# ESP_LoRa_Weather_1_55.net
KiCad netlist of a schematic drawn in EAGLE
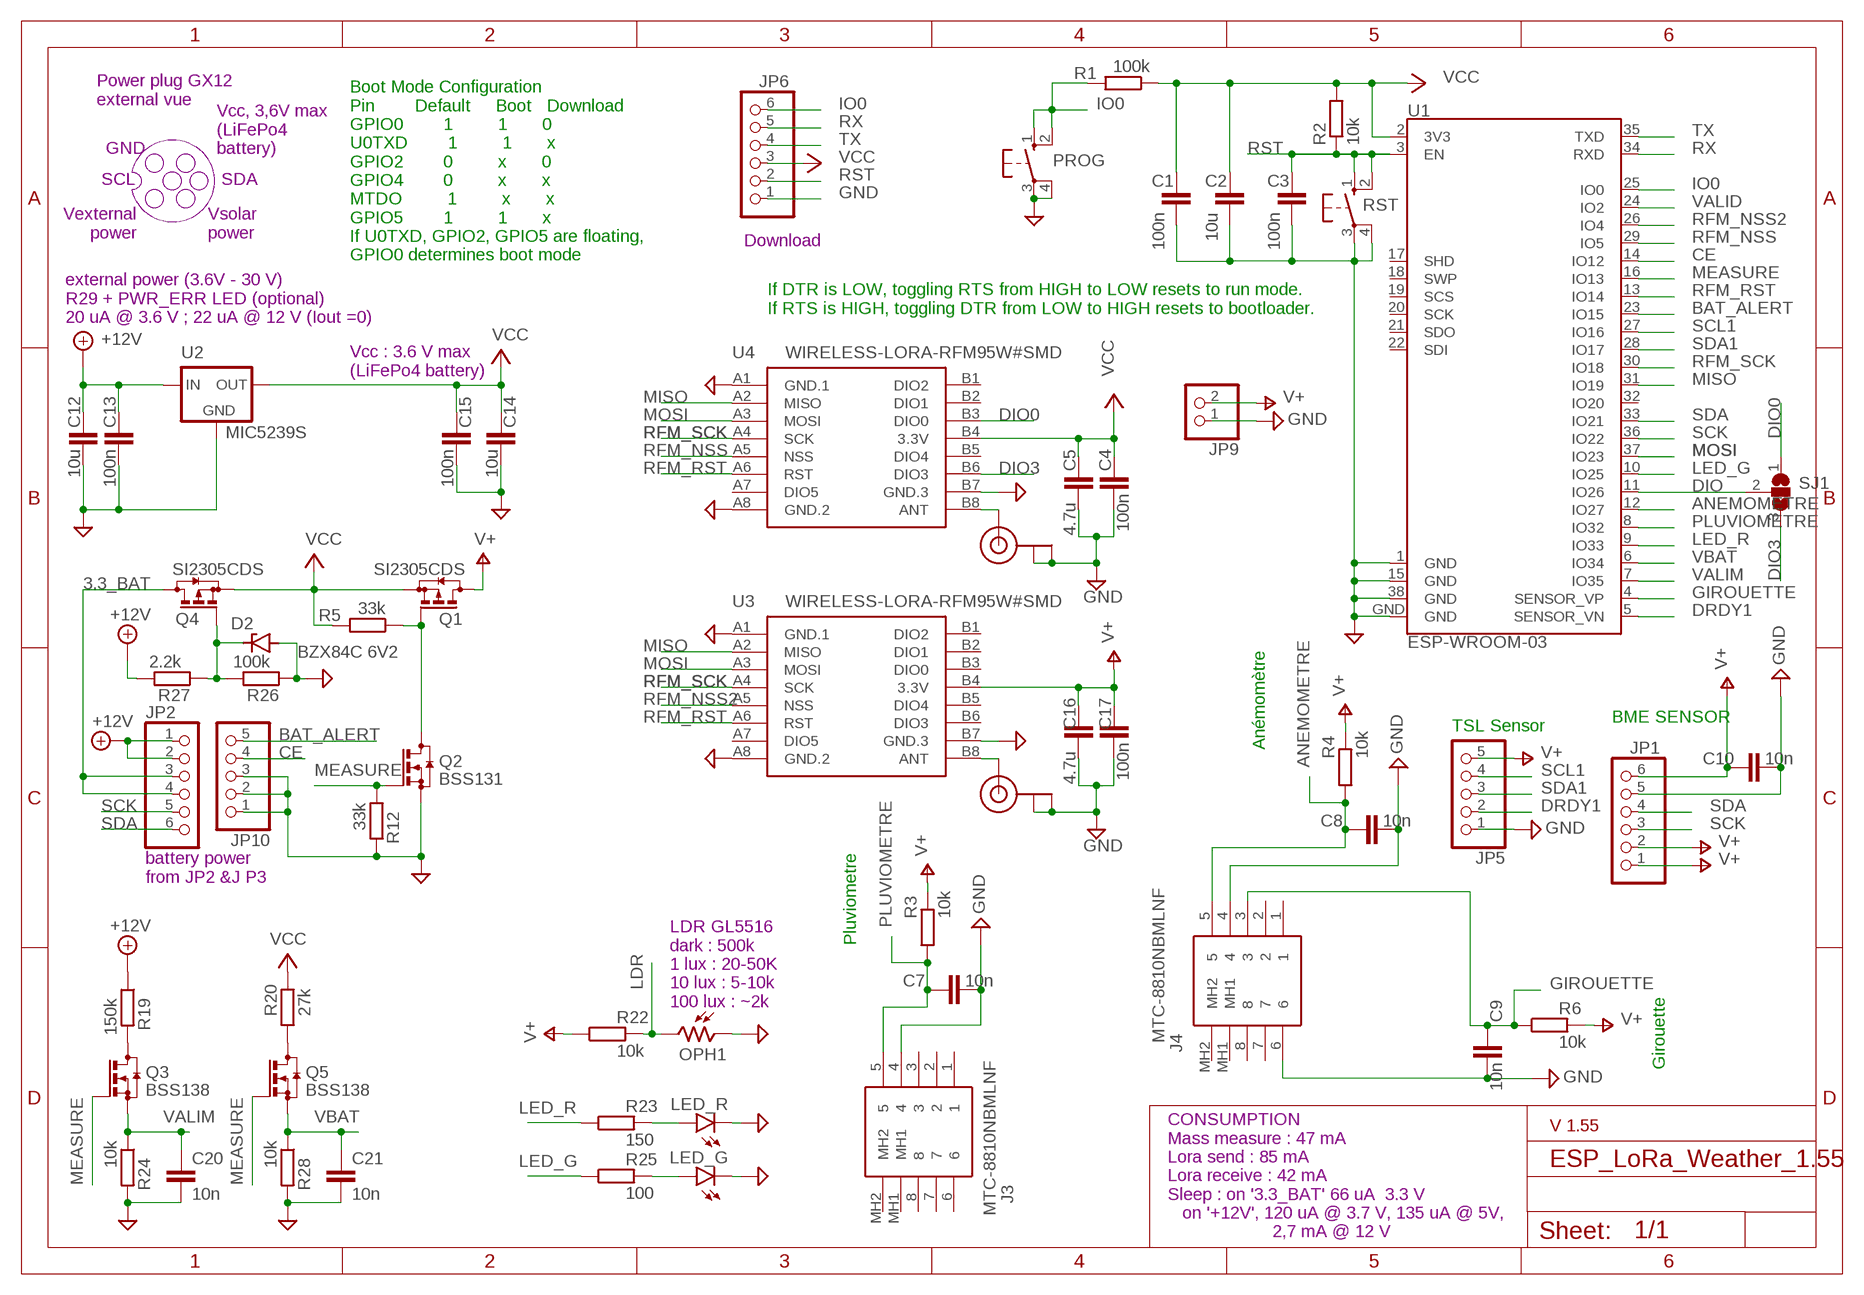
[diagram p0: schematic, sheet 1]

(export (version "E")
  (design (tool "Eeschema 10.0.6"))
  (components
    (comp (ref "C1")
      (value "100n")
      (footprint "eagle-import:C1206")
      (libsource (lib "eagle-import") (part "CC1206"))
    )
    (comp (ref "C2")
      (value "10u")
      (footprint "eagle-import:C1210")
      (libsource (lib "eagle-import") (part "CC1210"))
    )
    (comp (ref "C3")
      (value "100n")
      (footprint "eagle-import:C1206")
      (libsource (lib "eagle-import") (part "CC1206"))
    )
    (comp (ref "C4")
      (value "100n")
      (footprint "eagle-import:C1206")
      (libsource (lib "eagle-import") (part "CC1206"))
    )
    (comp (ref "C5")
      (value "4.7u")
      (footprint "eagle-import:C1210")
      (libsource (lib "eagle-import") (part "CC1210"))
    )
    (comp (ref "C7")
      (value "10n")
      (footprint "eagle-import:C1206")
      (libsource (lib "eagle-import") (part "CC1206"))
    )
    (comp (ref "C8")
      (value "10n")
      (footprint "eagle-import:C1206")
      (libsource (lib "eagle-import") (part "CC1206"))
    )
    (comp (ref "C9")
      (value "10n")
      (footprint "eagle-import:C1206")
      (libsource (lib "eagle-import") (part "CC1206"))
    )
    (comp (ref "C10")
      (value "10n")
      (footprint "eagle-import:C1206")
      (libsource (lib "eagle-import") (part "CC1206"))
    )
    (comp (ref "C12")
      (value "10u")
      (footprint "eagle-import:C1210")
      (libsource (lib "eagle-import") (part "CC1210"))
    )
    (comp (ref "C13")
      (value "100n")
      (footprint "eagle-import:C1206")
      (libsource (lib "eagle-import") (part "CC1206"))
    )
    (comp (ref "C14")
      (value "10u")
      (footprint "eagle-import:C1210")
      (libsource (lib "eagle-import") (part "CC1210"))
    )
    (comp (ref "C15")
      (value "100n")
      (footprint "eagle-import:C1206")
      (libsource (lib "eagle-import") (part "CC1206"))
    )
    (comp (ref "C16")
      (value "4.7u")
      (footprint "eagle-import:C1210")
      (libsource (lib "eagle-import") (part "CC1210"))
    )
    (comp (ref "C17")
      (value "100n")
      (footprint "eagle-import:C1206")
      (libsource (lib "eagle-import") (part "CC1206"))
    )
    (comp (ref "C20")
      (value "10n")
      (footprint "eagle-import:C1206")
      (libsource (lib "eagle-import") (part "CC1206"))
    )
    (comp (ref "C21")
      (value "10n")
      (footprint "eagle-import:C1206")
      (libsource (lib "eagle-import") (part "CC1206"))
    )
    (comp (ref "D2")
      (value "BZX84C 6V2")
      (footprint "eagle-import:TO236")
      (libsource (lib "eagle-import") (part "BZX84CSMD"))
    )
    (comp (ref "J1")
      (value "U.FL")
      (footprint "eagle-import:U.FL")
      (libsource (lib "eagle-import") (part "U.FL"))
    )
    (comp (ref "J2")
      (value "U.FL")
      (footprint "eagle-import:U.FL")
      (libsource (lib "eagle-import") (part "U.FL"))
    )
    (comp (ref "J3")
      (value "MTC-8810NBMLNF")
      (footprint "eagle-import:MTC8810NBMLNF")
      (libsource (lib "eagle-import") (part "MTC-8810NBMLNF"))
    )
    (comp (ref "J4")
      (value "MTC-8810NBMLNF")
      (footprint "eagle-import:MTC8810NBMLNF")
      (libsource (lib "eagle-import") (part "MTC-8810NBMLNF"))
    )
    (comp (ref "JP1")
      (value "PINHD-1X6")
      (footprint "eagle-import:1X06")
      (libsource (lib "eagle-import") (part "PINHD-1X6"))
    )
    (comp (ref "JP2")
      (value "PINHD-1X6")
      (footprint "eagle-import:1X06")
      (libsource (lib "eagle-import") (part "PINHD-1X6"))
    )
    (comp (ref "JP5")
      (value "PINHD-1X5")
      (footprint "eagle-import:1X05")
      (libsource (lib "eagle-import") (part "PINHD-1X5"))
    )
    (comp (ref "JP6")
      (value "PINHD-1X6")
      (footprint "eagle-import:1X06")
      (libsource (lib "eagle-import") (part "PINHD-1X6"))
    )
    (comp (ref "JP9")
      (value "PINHD-1X2")
      (footprint "eagle-import:1X02")
      (libsource (lib "eagle-import") (part "PINHD-1X2"))
    )
    (comp (ref "JP10")
      (value "PINHD-1X5")
      (footprint "eagle-import:1X05")
      (libsource (lib "eagle-import") (part "PINHD-1X5"))
    )
    (comp (ref "LED_G")
      (value "LEDSMT1206")
      (footprint "eagle-import:1206")
      (libsource (lib "eagle-import") (part "LEDSMT1206"))
    )
    (comp (ref "LED_R")
      (value "LEDSMT1206")
      (footprint "eagle-import:1206")
      (libsource (lib "eagle-import") (part "LEDSMT1206"))
    )
    (comp (ref "OPH1")
      (value "VT93N2")
      (footprint "eagle-import:VT900")
      (libsource (lib "eagle-import") (part "VT93N2"))
    )
    (comp (ref "PROG")
      (value "10-XX")
      (footprint "eagle-import:B3F-10XX")
      (fields (field (name "MPN") "B3F-1000"))
      (libsource (lib "eagle-import") (part "10-XX"))
    )
    (comp (ref "Q1")
      (value "SI2305CDS")
      (footprint "eagle-import:SOT23")
      (libsource (lib "eagle-import") (part "SI2305CDS"))
    )
    (comp (ref "Q2")
      (value "BSS131")
      (footprint "eagle-import:SOT23")
      (libsource (lib "eagle-import") (part "BSS131"))
    )
    (comp (ref "Q3")
      (value "BSS138")
      (footprint "eagle-import:SOT23")
      (libsource (lib "eagle-import") (part "BSS138"))
    )
    (comp (ref "Q4")
      (value "SI2305CDS")
      (footprint "eagle-import:SOT23")
      (libsource (lib "eagle-import") (part "SI2305CDS"))
    )
    (comp (ref "Q5")
      (value "BSS138")
      (footprint "eagle-import:SOT23")
      (libsource (lib "eagle-import") (part "BSS138"))
    )
    (comp (ref "R1")
      (value "100k")
      (footprint "eagle-import:R1206")
      (libsource (lib "eagle-import") (part "RR1206"))
    )
    (comp (ref "R2")
      (value "10k")
      (footprint "eagle-import:R1206")
      (libsource (lib "eagle-import") (part "RR1206"))
    )
    (comp (ref "R3")
      (value "10k")
      (footprint "eagle-import:R1206")
      (libsource (lib "eagle-import") (part "RR1206"))
    )
    (comp (ref "R4")
      (value "10k")
      (footprint "eagle-import:R1206")
      (libsource (lib "eagle-import") (part "RR1206"))
    )
    (comp (ref "R5")
      (value "33k")
      (footprint "eagle-import:R1206")
      (libsource (lib "eagle-import") (part "RR1206"))
    )
    (comp (ref "R6")
      (value "10k")
      (footprint "eagle-import:R1206")
      (libsource (lib "eagle-import") (part "RR1206"))
    )
    (comp (ref "R12")
      (value "33k")
      (footprint "eagle-import:R1206")
      (libsource (lib "eagle-import") (part "RR1206"))
    )
    (comp (ref "R19")
      (value "150k")
      (footprint "eagle-import:R1206")
      (libsource (lib "eagle-import") (part "RR1206"))
    )
    (comp (ref "R20")
      (value "27k")
      (footprint "eagle-import:R1206")
      (libsource (lib "eagle-import") (part "RR1206"))
    )
    (comp (ref "R22")
      (value "10k")
      (footprint "eagle-import:R1206")
      (libsource (lib "eagle-import") (part "RR1206"))
    )
    (comp (ref "R23")
      (value "150")
      (footprint "eagle-import:R1206")
      (libsource (lib "eagle-import") (part "RR1206"))
    )
    (comp (ref "R24")
      (value "10k")
      (footprint "eagle-import:R1206")
      (libsource (lib "eagle-import") (part "RR1206"))
    )
    (comp (ref "R25")
      (value "100")
      (footprint "eagle-import:R1206")
      (libsource (lib "eagle-import") (part "RR1206"))
    )
    (comp (ref "R26")
      (value "100k")
      (footprint "eagle-import:R1206")
      (libsource (lib "eagle-import") (part "RR1206"))
    )
    (comp (ref "R27")
      (value "2.2k")
      (footprint "eagle-import:R1206")
      (libsource (lib "eagle-import") (part "RR1206"))
    )
    (comp (ref "R28")
      (value "10k")
      (footprint "eagle-import:R1206")
      (libsource (lib "eagle-import") (part "RR1206"))
    )
    (comp (ref "RST")
      (value "10-XX")
      (footprint "eagle-import:B3F-10XX")
      (fields (field (name "MPN") "B3F-1000"))
      (libsource (lib "eagle-import") (part "10-XX"))
    )
    (comp (ref "SJ1")
      (value "SJ2W")
      (footprint "eagle-import:SJ_2")
      (libsource (lib "eagle-import") (part "SJ2W"))
    )
    (comp (ref "U1")
      (value "ESP-WROOM-03")
      (footprint "eagle-import:ESP-WROOM-03")
      (libsource (lib "eagle-import") (part "ESP-WROOM-03"))
    )
    (comp (ref "U2")
      (value "MIC5239S")
      (footprint "eagle-import:SOT223")
      (libsource (lib "eagle-import") (part "MIC5239S"))
    )
    (comp (ref "U3")
      (value "WIRELESS-LORA-RFM95W#SMD")
      (footprint "eagle-import:WIRELESS-LORA-RFM95W#SMD")
      (libsource (lib "eagle-import") (part "WIRELESS-LORA-RFM95W#SMD"))
    )
    (comp (ref "U4")
      (value "WIRELESS-LORA-RFM95W#SMD")
      (footprint "eagle-import:WIRELESS-LORA-RFM95W#SMD")
      (libsource (lib "eagle-import") (part "WIRELESS-LORA-RFM95W#SMD"))
    )
  )
  (nets
    (net (code "1") (name "+12V") (class "Default")
      (node (ref "C12") (pin "1") (pinfunction "1_1") (pintype "passive"))
      (node (ref "C13") (pin "1") (pinfunction "1_1") (pintype "passive"))
      (node (ref "JP2") (pin "1") (pinfunction "1_1") (pintype "passive"))
      (node (ref "JP2") (pin "2") (pinfunction "2_2") (pintype "passive"))
      (node (ref "R19") (pin "1") (pinfunction "1_1") (pintype "passive"))
      (node (ref "R27") (pin "2") (pinfunction "2_2") (pintype "passive"))
      (node (ref "U2") (pin "1") (pinfunction "IN_1") (pintype "input"))
    )
    (net (code "2") (name "/3.3_BAT") (class "Default")
      (node (ref "JP2") (pin "3") (pinfunction "3_3") (pintype "passive"))
      (node (ref "JP2") (pin "4") (pinfunction "4_4") (pintype "passive"))
      (node (ref "Q4") (pin "3") (pinfunction "D_3") (pintype "passive"))
    )
    (net (code "3") (name "/ANEMOMETRE") (class "Default")
      (node (ref "C8") (pin "1") (pinfunction "1_1") (pintype "passive"))
      (node (ref "J4") (pin "5") (pinfunction "5_5") (pintype "bidirectional"))
      (node (ref "R4") (pin "1") (pinfunction "1_1") (pintype "passive"))
      (node (ref "U1") (pin "12") (pinfunction "IO27_12") (pintype "bidirectional"))
    )
    (net (code "4") (name "/BAT_ALERT") (class "Default")
      (node (ref "JP10") (pin "5") (pinfunction "5_5") (pintype "passive"))
      (node (ref "U1") (pin "23") (pinfunction "IO15_23") (pintype "bidirectional"))
    )
    (net (code "5") (name "/CE") (class "Default")
      (node (ref "JP10") (pin "4") (pinfunction "4_4") (pintype "passive"))
      (node (ref "U1") (pin "14") (pinfunction "IO12_14") (pintype "bidirectional"))
    )
    (net (code "6") (name "/DIO") (class "Default")
      (node (ref "SJ1") (pin "2") (pinfunction "2_2") (pintype "passive"))
      (node (ref "U1") (pin "11") (pinfunction "IO26_11") (pintype "bidirectional"))
    )
    (net (code "7") (name "/DIO0") (class "Default")
      (node (ref "SJ1") (pin "1") (pinfunction "1_1") (pintype "passive"))
      (node (ref "U4") (pin "B3") (pinfunction "DIO0_B3") (pintype "bidirectional"))
    )
    (net (code "8") (name "/DIO3") (class "Default")
      (node (ref "SJ1") (pin "3") (pinfunction "3_3") (pintype "passive"))
      (node (ref "U4") (pin "B6") (pinfunction "DIO3_B6") (pintype "bidirectional"))
    )
    (net (code "9") (name "/DRDY1") (class "Default")
      (node (ref "JP5") (pin "2") (pinfunction "2_2") (pintype "passive"))
      (node (ref "U1") (pin "5") (pinfunction "SENSOR_VN_5") (pintype "bidirectional"))
    )
    (net (code "10") (name "/GIROUETTE") (class "Default")
      (node (ref "C9") (pin "1") (pinfunction "1_1") (pintype "passive"))
      (node (ref "J4") (pin "3") (pinfunction "3_3") (pintype "bidirectional"))
      (node (ref "R6") (pin "1") (pinfunction "1_1") (pintype "passive"))
      (node (ref "U1") (pin "4") (pinfunction "SENSOR_VP_4") (pintype "bidirectional"))
    )
    (net (code "11") (name "/IO0") (class "Default")
      (node (ref "JP6") (pin "6") (pinfunction "6_6") (pintype "passive"))
      (node (ref "PROG") (pin "1") (pinfunction "S_1") (pintype "passive"))
      (node (ref "PROG") (pin "2") (pinfunction "S1_2") (pintype "passive"))
      (node (ref "R1") (pin "2") (pinfunction "2_2") (pintype "passive"))
      (node (ref "U1") (pin "25") (pinfunction "IO0_25") (pintype "bidirectional"))
    )
    (net (code "12") (name "/LDR") (class "Default")
      (node (ref "OPH1") (pin "2") (pinfunction "2_2") (pintype "passive"))
      (node (ref "R22") (pin "2") (pinfunction "2_2") (pintype "passive"))
    )
    (net (code "13") (name "/LED_G") (class "Default")
      (node (ref "R25") (pin "1") (pinfunction "1_1") (pintype "passive"))
      (node (ref "U1") (pin "10") (pinfunction "IO25_10") (pintype "bidirectional"))
    )
    (net (code "14") (name "/LED_R") (class "Default")
      (node (ref "R23") (pin "1") (pinfunction "1_1") (pintype "passive"))
      (node (ref "U1") (pin "9") (pinfunction "IO33_9") (pintype "bidirectional"))
    )
    (net (code "15") (name "/MEASURE") (class "Default")
      (node (ref "Q2") (pin "1") (pinfunction "G_1") (pintype "passive"))
      (node (ref "Q3") (pin "1") (pinfunction "G_1") (pintype "passive"))
      (node (ref "Q5") (pin "1") (pinfunction "G_1") (pintype "passive"))
      (node (ref "R12") (pin "1") (pinfunction "1_1") (pintype "passive"))
      (node (ref "U1") (pin "16") (pinfunction "IO13_16") (pintype "bidirectional"))
    )
    (net (code "16") (name "/MISO") (class "Default")
      (node (ref "U1") (pin "31") (pinfunction "IO19_31") (pintype "bidirectional"))
      (node (ref "U3") (pin "A2") (pinfunction "MISO_A2") (pintype "bidirectional"))
      (node (ref "U4") (pin "A2") (pinfunction "MISO_A2") (pintype "bidirectional"))
    )
    (net (code "17") (name "/MOSI") (class "Default")
      (node (ref "U1") (pin "37") (pinfunction "IO23_37") (pintype "bidirectional"))
      (node (ref "U3") (pin "A3") (pinfunction "MOSI_A3") (pintype "bidirectional"))
      (node (ref "U4") (pin "A3") (pinfunction "MOSI_A3") (pintype "bidirectional"))
    )
    (net (code "18") (name "/PLUVIOMETRE") (class "Default")
      (node (ref "C7") (pin "1") (pinfunction "1_1") (pintype "passive"))
      (node (ref "J3") (pin "5") (pinfunction "5_5") (pintype "bidirectional"))
      (node (ref "R3") (pin "1") (pinfunction "1_1") (pintype "passive"))
      (node (ref "U1") (pin "8") (pinfunction "IO32_8") (pintype "bidirectional"))
    )
    (net (code "19") (name "/RFM_NSS") (class "Default")
      (node (ref "U1") (pin "29") (pinfunction "IO5_29") (pintype "bidirectional"))
      (node (ref "U4") (pin "A5") (pinfunction "NSS_A5") (pintype "bidirectional"))
    )
    (net (code "20") (name "/RFM_NSS2") (class "Default")
      (node (ref "U1") (pin "26") (pinfunction "IO4_26") (pintype "bidirectional"))
      (node (ref "U3") (pin "A5") (pinfunction "NSS_A5") (pintype "bidirectional"))
    )
    (net (code "21") (name "/RFM_RST") (class "Default")
      (node (ref "U1") (pin "13") (pinfunction "IO14_13") (pintype "bidirectional"))
      (node (ref "U3") (pin "A6") (pinfunction "RST_A6") (pintype "bidirectional"))
      (node (ref "U4") (pin "A6") (pinfunction "RST_A6") (pintype "bidirectional"))
    )
    (net (code "22") (name "/RFM_SCK") (class "Default")
      (node (ref "U1") (pin "30") (pinfunction "IO18_30") (pintype "bidirectional"))
      (node (ref "U3") (pin "A4") (pinfunction "SCK_A4") (pintype "bidirectional"))
      (node (ref "U4") (pin "A4") (pinfunction "SCK_A4") (pintype "bidirectional"))
    )
    (net (code "23") (name "/RST") (class "Default")
      (node (ref "C3") (pin "1") (pinfunction "1_1") (pintype "passive"))
      (node (ref "JP6") (pin "2") (pinfunction "2_2") (pintype "passive"))
      (node (ref "R2") (pin "1") (pinfunction "1_1") (pintype "passive"))
      (node (ref "RST") (pin "1") (pinfunction "S_1") (pintype "passive"))
      (node (ref "RST") (pin "2") (pinfunction "S1_2") (pintype "passive"))
      (node (ref "U1") (pin "3") (pinfunction "EN_3") (pintype "bidirectional"))
    )
    (net (code "24") (name "/RX") (class "Default")
      (node (ref "JP6") (pin "5") (pinfunction "5_5") (pintype "passive"))
      (node (ref "U1") (pin "34") (pinfunction "RXD_34") (pintype "bidirectional"))
    )
    (net (code "25") (name "/SCK") (class "Default")
      (node (ref "JP1") (pin "3") (pinfunction "3_3") (pintype "passive"))
      (node (ref "JP2") (pin "5") (pinfunction "5_5") (pintype "passive"))
      (node (ref "U1") (pin "36") (pinfunction "IO22_36") (pintype "bidirectional"))
    )
    (net (code "26") (name "/SCL1") (class "Default")
      (node (ref "JP5") (pin "4") (pinfunction "4_4") (pintype "passive"))
      (node (ref "U1") (pin "27") (pinfunction "IO16_27") (pintype "bidirectional"))
    )
    (net (code "27") (name "/SDA") (class "Default")
      (node (ref "JP1") (pin "4") (pinfunction "4_4") (pintype "passive"))
      (node (ref "JP2") (pin "6") (pinfunction "6_6") (pintype "passive"))
      (node (ref "U1") (pin "33") (pinfunction "IO21_33") (pintype "bidirectional"))
    )
    (net (code "28") (name "/SDA1") (class "Default")
      (node (ref "JP5") (pin "3") (pinfunction "3_3") (pintype "passive"))
      (node (ref "U1") (pin "28") (pinfunction "IO17_28") (pintype "bidirectional"))
    )
    (net (code "29") (name "/TX") (class "Default")
      (node (ref "JP6") (pin "4") (pinfunction "4_4") (pintype "passive"))
      (node (ref "U1") (pin "35") (pinfunction "TXD_35") (pintype "bidirectional"))
    )
    (net (code "30") (name "/VALID") (class "Default")
      (node (ref "U1") (pin "24") (pinfunction "IO2_24") (pintype "bidirectional"))
    )
    (net (code "31") (name "/VALIM") (class "Default")
      (node (ref "C20") (pin "1") (pinfunction "1_1") (pintype "passive"))
      (node (ref "Q3") (pin "2") (pinfunction "S_2") (pintype "passive"))
      (node (ref "R24") (pin "1") (pinfunction "1_1") (pintype "passive"))
      (node (ref "U1") (pin "7") (pinfunction "IO35_7") (pintype "bidirectional"))
    )
    (net (code "32") (name "/VBAT") (class "Default")
      (node (ref "C21") (pin "1") (pinfunction "1_1") (pintype "passive"))
      (node (ref "Q5") (pin "2") (pinfunction "S_2") (pintype "passive"))
      (node (ref "R28") (pin "1") (pinfunction "1_1") (pintype "passive"))
      (node (ref "U1") (pin "6") (pinfunction "IO34_6") (pintype "bidirectional"))
    )
    (net (code "33") (name "GND") (class "Default")
      (node (ref "C1") (pin "2") (pinfunction "2_2") (pintype "passive"))
      (node (ref "C10") (pin "2") (pinfunction "2_2") (pintype "passive"))
      (node (ref "C12") (pin "2") (pinfunction "2_2") (pintype "passive"))
      (node (ref "C13") (pin "2") (pinfunction "2_2") (pintype "passive"))
      (node (ref "C14") (pin "2") (pinfunction "2_2") (pintype "passive"))
      (node (ref "C15") (pin "2") (pinfunction "2_2") (pintype "passive"))
      (node (ref "C16") (pin "2") (pinfunction "2_2") (pintype "passive"))
      (node (ref "C17") (pin "2") (pinfunction "2_2") (pintype "passive"))
      (node (ref "C2") (pin "2") (pinfunction "2_2") (pintype "passive"))
      (node (ref "C20") (pin "2") (pinfunction "2_2") (pintype "passive"))
      (node (ref "C21") (pin "2") (pinfunction "2_2") (pintype "passive"))
      (node (ref "C3") (pin "2") (pinfunction "2_2") (pintype "passive"))
      (node (ref "C4") (pin "2") (pinfunction "2_2") (pintype "passive"))
      (node (ref "C5") (pin "2") (pinfunction "2_2") (pintype "passive"))
      (node (ref "C7") (pin "2") (pinfunction "2_2") (pintype "passive"))
      (node (ref "C8") (pin "2") (pinfunction "2_2") (pintype "passive"))
      (node (ref "C9") (pin "2") (pinfunction "2_2") (pintype "passive"))
      (node (ref "D2") (pin "A") (pinfunction "A_A") (pintype "passive"))
      (node (ref "J1") (pin "1") (pinfunction "GND_1") (pintype "passive"))
      (node (ref "J1") (pin "2") (pinfunction "GND_2") (pintype "passive"))
      (node (ref "J2") (pin "1") (pinfunction "GND_1") (pintype "passive"))
      (node (ref "J2") (pin "2") (pinfunction "GND_2") (pintype "passive"))
      (node (ref "J3") (pin "4") (pinfunction "4_4") (pintype "bidirectional"))
      (node (ref "J4") (pin "4") (pinfunction "4_4") (pintype "bidirectional"))
      (node (ref "J4") (pin "6") (pinfunction "6_6") (pintype "bidirectional"))
      (node (ref "JP1") (pin "5") (pinfunction "5_5") (pintype "passive"))
      (node (ref "JP10") (pin "1") (pinfunction "1_1") (pintype "passive"))
      (node (ref "JP10") (pin "2") (pinfunction "2_2") (pintype "passive"))
      (node (ref "JP10") (pin "3") (pinfunction "3_3") (pintype "passive"))
      (node (ref "JP5") (pin "1") (pinfunction "1_1") (pintype "passive"))
      (node (ref "JP6") (pin "1") (pinfunction "1_1") (pintype "passive"))
      (node (ref "JP9") (pin "1") (pinfunction "1_1") (pintype "passive"))
      (node (ref "LED_G") (pin "C") (pinfunction "C_C") (pintype "passive"))
      (node (ref "LED_R") (pin "C") (pinfunction "C_C") (pintype "passive"))
      (node (ref "OPH1") (pin "1") (pinfunction "1_1") (pintype "passive"))
      (node (ref "PROG") (pin "3") (pinfunction "P_3") (pintype "passive"))
      (node (ref "PROG") (pin "4") (pinfunction "P1_4") (pintype "passive"))
      (node (ref "Q2") (pin "2") (pinfunction "S_2") (pintype "passive"))
      (node (ref "R12") (pin "2") (pinfunction "2_2") (pintype "passive"))
      (node (ref "R24") (pin "2") (pinfunction "2_2") (pintype "passive"))
      (node (ref "R26") (pin "1") (pinfunction "1_1") (pintype "passive"))
      (node (ref "R28") (pin "2") (pinfunction "2_2") (pintype "passive"))
      (node (ref "RST") (pin "3") (pinfunction "P_3") (pintype "passive"))
      (node (ref "RST") (pin "4") (pinfunction "P1_4") (pintype "passive"))
      (node (ref "U1") (pin "1") (pinfunction "GND_1") (pintype "bidirectional"))
      (node (ref "U1") (pin "15") (pinfunction "GND_15") (pintype "bidirectional"))
      (node (ref "U1") (pin "38") (pinfunction "GND_38") (pintype "bidirectional"))
      (node (ref "U1") (pin "GND") (pinfunction "GND_GND") (pintype "bidirectional"))
      (node (ref "U2") (pin "2") (pinfunction "GND_2") (pintype "passive"))
      (node (ref "U2") (pin "4") (pinfunction "GND_4") (pintype "passive"))
      (node (ref "U3") (pin "A1") (pinfunction "GND.1_A1") (pintype "power_in"))
      (node (ref "U3") (pin "A8") (pinfunction "GND.2_A8") (pintype "power_in"))
      (node (ref "U3") (pin "B7") (pinfunction "GND.3_B7") (pintype "power_in"))
      (node (ref "U4") (pin "A1") (pinfunction "GND.1_A1") (pintype "power_in"))
      (node (ref "U4") (pin "A8") (pinfunction "GND.2_A8") (pintype "power_in"))
      (node (ref "U4") (pin "B7") (pinfunction "GND.3_B7") (pintype "power_in"))
    )
    (net (code "34") (name "Net-(J1-SIGNAL)") (class "Default")
      (node (ref "J1") (pin "3") (pinfunction "SIGNAL_3") (pintype "passive"))
      (node (ref "U3") (pin "B8") (pinfunction "ANT_B8") (pintype "passive"))
    )
    (net (code "35") (name "Net-(J2-SIGNAL)") (class "Default")
      (node (ref "J2") (pin "3") (pinfunction "SIGNAL_3") (pintype "passive"))
      (node (ref "U4") (pin "B8") (pinfunction "ANT_B8") (pintype "passive"))
    )
    (net (code "36") (name "Net-(LED_G-PadA)") (class "Default")
      (node (ref "LED_G") (pin "A") (pinfunction "A_A") (pintype "passive"))
      (node (ref "R25") (pin "2") (pinfunction "2_2") (pintype "passive"))
    )
    (net (code "37") (name "Net-(LED_R-PadA)") (class "Default")
      (node (ref "LED_R") (pin "A") (pinfunction "A_A") (pintype "passive"))
      (node (ref "R23") (pin "2") (pinfunction "2_2") (pintype "passive"))
    )
    (net (code "38") (name "Net-(Q1-G)") (class "Default")
      (node (ref "Q1") (pin "1") (pinfunction "G_1") (pintype "passive"))
      (node (ref "Q2") (pin "3") (pinfunction "D_3") (pintype "passive"))
      (node (ref "R5") (pin "1") (pinfunction "1_1") (pintype "passive"))
    )
    (net (code "39") (name "Net-(Q3-D)") (class "Default")
      (node (ref "Q3") (pin "3") (pinfunction "D_3") (pintype "passive"))
      (node (ref "R19") (pin "2") (pinfunction "2_2") (pintype "passive"))
    )
    (net (code "40") (name "Net-(Q4-G)") (class "Default")
      (node (ref "D2") (pin "C") (pinfunction "C_C") (pintype "passive"))
      (node (ref "Q4") (pin "1") (pinfunction "G_1") (pintype "passive"))
      (node (ref "R26") (pin "2") (pinfunction "2_2") (pintype "passive"))
      (node (ref "R27") (pin "1") (pinfunction "1_1") (pintype "passive"))
    )
    (net (code "41") (name "Net-(Q5-D)") (class "Default")
      (node (ref "Q5") (pin "3") (pinfunction "D_3") (pintype "passive"))
      (node (ref "R20") (pin "1") (pinfunction "1_1") (pintype "passive"))
    )
    (net (code "42") (name "V+") (class "Default")
      (node (ref "C10") (pin "1") (pinfunction "1_1") (pintype "passive"))
      (node (ref "C16") (pin "1") (pinfunction "1_1") (pintype "passive"))
      (node (ref "C17") (pin "1") (pinfunction "1_1") (pintype "passive"))
      (node (ref "JP1") (pin "1") (pinfunction "1_1") (pintype "passive"))
      (node (ref "JP1") (pin "2") (pinfunction "2_2") (pintype "passive"))
      (node (ref "JP1") (pin "6") (pinfunction "6_6") (pintype "passive"))
      (node (ref "JP5") (pin "5") (pinfunction "5_5") (pintype "passive"))
      (node (ref "JP9") (pin "2") (pinfunction "2_2") (pintype "passive"))
      (node (ref "Q1") (pin "3") (pinfunction "D_3") (pintype "passive"))
      (node (ref "R22") (pin "1") (pinfunction "1_1") (pintype "passive"))
      (node (ref "R3") (pin "2") (pinfunction "2_2") (pintype "passive"))
      (node (ref "R4") (pin "2") (pinfunction "2_2") (pintype "passive"))
      (node (ref "R6") (pin "2") (pinfunction "2_2") (pintype "passive"))
      (node (ref "U3") (pin "B4") (pinfunction "3.3V_B4") (pintype "power_in"))
    )
    (net (code "43") (name "VCC") (class "Default")
      (node (ref "C1") (pin "1") (pinfunction "1_1") (pintype "passive"))
      (node (ref "C14") (pin "1") (pinfunction "1_1") (pintype "passive"))
      (node (ref "C15") (pin "1") (pinfunction "1_1") (pintype "passive"))
      (node (ref "C2") (pin "1") (pinfunction "1_1") (pintype "passive"))
      (node (ref "C4") (pin "1") (pinfunction "1_1") (pintype "passive"))
      (node (ref "C5") (pin "1") (pinfunction "1_1") (pintype "passive"))
      (node (ref "JP6") (pin "3") (pinfunction "3_3") (pintype "passive"))
      (node (ref "Q1") (pin "2") (pinfunction "S_2") (pintype "passive"))
      (node (ref "Q4") (pin "2") (pinfunction "S_2") (pintype "passive"))
      (node (ref "R1") (pin "1") (pinfunction "1_1") (pintype "passive"))
      (node (ref "R2") (pin "2") (pinfunction "2_2") (pintype "passive"))
      (node (ref "R20") (pin "2") (pinfunction "2_2") (pintype "passive"))
      (node (ref "R5") (pin "2") (pinfunction "2_2") (pintype "passive"))
      (node (ref "U1") (pin "2") (pinfunction "3V3_2") (pintype "bidirectional"))
      (node (ref "U2") (pin "3") (pinfunction "OUT_3") (pintype "passive"))
      (node (ref "U4") (pin "B4") (pinfunction "3.3V_B4") (pintype "power_in"))
    )
    (net (code "44") (name "unconnected-(J3-Pad1)") (class "Default")
      (node (ref "J3") (pin "1") (pinfunction "1_1") (pintype "bidirectional"))
    )
    (net (code "45") (name "unconnected-(J3-Pad2)") (class "Default")
      (node (ref "J3") (pin "2") (pinfunction "2_2") (pintype "bidirectional"))
    )
    (net (code "46") (name "unconnected-(J3-Pad3)") (class "Default")
      (node (ref "J3") (pin "3") (pinfunction "3_3") (pintype "bidirectional"))
    )
    (net (code "47") (name "unconnected-(J3-Pad6)") (class "Default")
      (node (ref "J3") (pin "6") (pinfunction "6_6") (pintype "bidirectional"))
    )
    (net (code "48") (name "unconnected-(J3-Pad7)") (class "Default")
      (node (ref "J3") (pin "7") (pinfunction "7_7") (pintype "bidirectional"))
    )
    (net (code "49") (name "unconnected-(J3-Pad8)") (class "Default")
      (node (ref "J3") (pin "8") (pinfunction "8_8") (pintype "bidirectional"))
    )
    (net (code "50") (name "unconnected-(J3-PadMH1)") (class "Default")
      (node (ref "J3") (pin "MH1") (pinfunction "MH1_MH1") (pintype "bidirectional"))
    )
    (net (code "51") (name "unconnected-(J3-PadMH2)") (class "Default")
      (node (ref "J3") (pin "MH2") (pinfunction "MH2_MH2") (pintype "bidirectional"))
    )
    (net (code "52") (name "unconnected-(J4-Pad1)") (class "Default")
      (node (ref "J4") (pin "1") (pinfunction "1_1") (pintype "bidirectional"))
    )
    (net (code "53") (name "unconnected-(J4-Pad2)") (class "Default")
      (node (ref "J4") (pin "2") (pinfunction "2_2") (pintype "bidirectional"))
    )
    (net (code "54") (name "unconnected-(J4-Pad7)") (class "Default")
      (node (ref "J4") (pin "7") (pinfunction "7_7") (pintype "bidirectional"))
    )
    (net (code "55") (name "unconnected-(J4-Pad8)") (class "Default")
      (node (ref "J4") (pin "8") (pinfunction "8_8") (pintype "bidirectional"))
    )
    (net (code "56") (name "unconnected-(J4-PadMH1)") (class "Default")
      (node (ref "J4") (pin "MH1") (pinfunction "MH1_MH1") (pintype "bidirectional"))
    )
    (net (code "57") (name "unconnected-(J4-PadMH2)") (class "Default")
      (node (ref "J4") (pin "MH2") (pinfunction "MH2_MH2") (pintype "bidirectional"))
    )
    (net (code "58") (name "unconnected-(U1-IO20-Pad32)") (class "Default")
      (node (ref "U1") (pin "32") (pinfunction "IO20_32") (pintype "bidirectional"))
    )
    (net (code "59") (name "unconnected-(U1-SCK-Pad20)") (class "Default")
      (node (ref "U1") (pin "20") (pinfunction "SCK_20") (pintype "bidirectional"))
    )
    (net (code "60") (name "unconnected-(U1-SCS-Pad19)") (class "Default")
      (node (ref "U1") (pin "19") (pinfunction "SCS_19") (pintype "bidirectional"))
    )
    (net (code "61") (name "unconnected-(U1-SDI-Pad22)") (class "Default")
      (node (ref "U1") (pin "22") (pinfunction "SDI_22") (pintype "bidirectional"))
    )
    (net (code "62") (name "unconnected-(U1-SDO-Pad21)") (class "Default")
      (node (ref "U1") (pin "21") (pinfunction "SDO_21") (pintype "bidirectional"))
    )
    (net (code "63") (name "unconnected-(U1-SHD-Pad17)") (class "Default")
      (node (ref "U1") (pin "17") (pinfunction "SHD_17") (pintype "bidirectional"))
    )
    (net (code "64") (name "unconnected-(U1-SWP-Pad18)") (class "Default")
      (node (ref "U1") (pin "18") (pinfunction "SWP_18") (pintype "bidirectional"))
    )
    (net (code "65") (name "unconnected-(U3-DIO0-PadB3)") (class "Default")
      (node (ref "U3") (pin "B3") (pinfunction "DIO0_B3") (pintype "bidirectional"))
    )
    (net (code "66") (name "unconnected-(U3-DIO1-PadB2)") (class "Default")
      (node (ref "U3") (pin "B2") (pinfunction "DIO1_B2") (pintype "bidirectional"))
    )
    (net (code "67") (name "unconnected-(U3-DIO2-PadB1)") (class "Default")
      (node (ref "U3") (pin "B1") (pinfunction "DIO2_B1") (pintype "bidirectional"))
    )
    (net (code "68") (name "unconnected-(U3-DIO3-PadB6)") (class "Default")
      (node (ref "U3") (pin "B6") (pinfunction "DIO3_B6") (pintype "bidirectional"))
    )
    (net (code "69") (name "unconnected-(U3-DIO4-PadB5)") (class "Default")
      (node (ref "U3") (pin "B5") (pinfunction "DIO4_B5") (pintype "bidirectional"))
    )
    (net (code "70") (name "unconnected-(U3-DIO5-PadA7)") (class "Default")
      (node (ref "U3") (pin "A7") (pinfunction "DIO5_A7") (pintype "bidirectional"))
    )
    (net (code "71") (name "unconnected-(U4-DIO1-PadB2)") (class "Default")
      (node (ref "U4") (pin "B2") (pinfunction "DIO1_B2") (pintype "bidirectional"))
    )
    (net (code "72") (name "unconnected-(U4-DIO2-PadB1)") (class "Default")
      (node (ref "U4") (pin "B1") (pinfunction "DIO2_B1") (pintype "bidirectional"))
    )
    (net (code "73") (name "unconnected-(U4-DIO4-PadB5)") (class "Default")
      (node (ref "U4") (pin "B5") (pinfunction "DIO4_B5") (pintype "bidirectional"))
    )
    (net (code "74") (name "unconnected-(U4-DIO5-PadA7)") (class "Default")
      (node (ref "U4") (pin "A7") (pinfunction "DIO5_A7") (pintype "bidirectional"))
    )
  )
)
